# motor_drive.net
KiCad netlist of a schematic drawn in Altium Designer
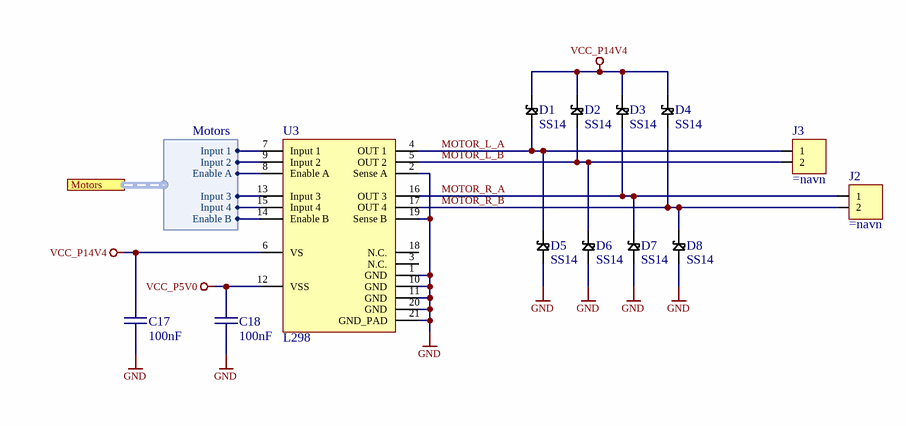
[diagram p0: motor_drive.SchDoc]

(export (version "E")
  (design (tool "Eeschema 10.0.6"))
  (components
    (comp (ref "C17")
      (value "100nF")
      (footprint "CAPC0603(1608)55_N")
      (description "X7R 50V 5%")
      (libsource (lib "OVLib_64") (part "CAP"))
    )
    (comp (ref "C18")
      (value "100nF")
      (footprint "CAPC0603(1608)55_N")
      (description "X7R 50V 5%")
      (libsource (lib "OVLib_64") (part "CAP"))
    )
    (comp (ref "D1")
      (value "SS14")
      (footprint "SMA_DO-214AC")
      (libsource (lib "OVLib_64") (part "SchottkyDiode"))
    )
    (comp (ref "D2")
      (value "SS14")
      (footprint "SMA_DO-214AC")
      (libsource (lib "OVLib_64") (part "SchottkyDiode"))
    )
    (comp (ref "D3")
      (value "SS14")
      (footprint "SMA_DO-214AC")
      (libsource (lib "OVLib_64") (part "SchottkyDiode"))
    )
    (comp (ref "D4")
      (value "SS14")
      (footprint "SMA_DO-214AC")
      (libsource (lib "OVLib_64") (part "SchottkyDiode"))
    )
    (comp (ref "D5")
      (value "SS14")
      (footprint "SMA_DO-214AC")
      (libsource (lib "OVLib_64") (part "SchottkyDiode"))
    )
    (comp (ref "D6")
      (value "SS14")
      (footprint "SMA_DO-214AC")
      (libsource (lib "OVLib_64") (part "SchottkyDiode"))
    )
    (comp (ref "D7")
      (value "SS14")
      (footprint "SMA_DO-214AC")
      (libsource (lib "OVLib_64") (part "SchottkyDiode"))
    )
    (comp (ref "D8")
      (value "SS14")
      (footprint "SMA_DO-214AC")
      (libsource (lib "OVLib_64") (part "SchottkyDiode"))
    )
    (comp (ref "J2")
      (value "~")
      (footprint "XT30_Female_Vertical")
      (description "Pris per del, For å koble ledninger sammen")
      (libsource (lib "OVLib_64") (part "2PConnector"))
    )
    (comp (ref "J3")
      (value "~")
      (footprint "XT30_Female_Vertical")
      (description "Pris per del, For å koble ledninger sammen")
      (libsource (lib "OVLib_64") (part "2PConnector"))
    )
    (comp (ref "U3")
      (value "L298")
      (footprint "SOIC127P1420X360_HS-21M")
      (description "Dual H Bridge")
      (libsource (lib "OVLib_64") (part "L298"))
    )
  )
  (nets
    (net (code "2") (name "/Enable A") (class "Default")
      (node (ref "U3") (pin "8") (pinfunction "Enable_A_8") (pintype "passive"))
    )
    (net (code "3") (name "/Enable B") (class "Default")
      (node (ref "U3") (pin "14") (pinfunction "Enable_B_14") (pintype "passive"))
    )
    (net (code "4") (name "/Input 1") (class "Default")
      (node (ref "U3") (pin "7") (pinfunction "Input_1_7") (pintype "passive"))
    )
    (net (code "5") (name "/Input 2") (class "Default")
      (node (ref "U3") (pin "9") (pinfunction "Input_2_9") (pintype "passive"))
    )
    (net (code "6") (name "/Input 3") (class "Default")
      (node (ref "U3") (pin "13") (pinfunction "Input_3_13") (pintype "passive"))
    )
    (net (code "7") (name "/Input 4") (class "Default")
      (node (ref "U3") (pin "15") (pinfunction "Input_4_15") (pintype "passive"))
    )
    (net (code "8") (name "/MOTOR_L_A") (class "Default")
      (node (ref "D1") (pin "1") (pinfunction "A_1") (pintype "passive"))
      (node (ref "D5") (pin "2") (pinfunction "K_2") (pintype "passive"))
      (node (ref "J3") (pin "1") (pinfunction "1_1") (pintype "passive"))
      (node (ref "U3") (pin "4") (pinfunction "OUT_1_4") (pintype "passive"))
    )
    (net (code "9") (name "/MOTOR_L_B") (class "Default")
      (node (ref "D2") (pin "1") (pinfunction "A_1") (pintype "passive"))
      (node (ref "D6") (pin "2") (pinfunction "K_2") (pintype "passive"))
      (node (ref "J3") (pin "2") (pinfunction "2_2") (pintype "passive"))
      (node (ref "U3") (pin "5") (pinfunction "OUT_2_5") (pintype "passive"))
    )
    (net (code "10") (name "/MOTOR_R_A") (class "Default")
      (node (ref "D3") (pin "1") (pinfunction "A_1") (pintype "passive"))
      (node (ref "D7") (pin "2") (pinfunction "K_2") (pintype "passive"))
      (node (ref "J2") (pin "1") (pinfunction "1_1") (pintype "passive"))
      (node (ref "U3") (pin "16") (pinfunction "OUT_3_16") (pintype "passive"))
    )
    (net (code "11") (name "/MOTOR_R_B") (class "Default")
      (node (ref "D4") (pin "1") (pinfunction "A_1") (pintype "passive"))
      (node (ref "D8") (pin "2") (pinfunction "K_2") (pintype "passive"))
      (node (ref "J2") (pin "2") (pinfunction "2_2") (pintype "passive"))
      (node (ref "U3") (pin "17") (pinfunction "OUT_4_17") (pintype "passive"))
    )
    (net (code "13") (name "GND") (class "Default")
      (node (ref "C17") (pin "1") (pinfunction "1_1") (pintype "passive"))
      (node (ref "C18") (pin "1") (pinfunction "1_1") (pintype "passive"))
      (node (ref "D5") (pin "1") (pinfunction "A_1") (pintype "passive"))
      (node (ref "D6") (pin "1") (pinfunction "A_1") (pintype "passive"))
      (node (ref "D7") (pin "1") (pinfunction "A_1") (pintype "passive"))
      (node (ref "D8") (pin "1") (pinfunction "A_1") (pintype "passive"))
      (node (ref "U3") (pin "1") (pinfunction "GND_1") (pintype "passive"))
      (node (ref "U3") (pin "10") (pinfunction "GND_10") (pintype "passive"))
      (node (ref "U3") (pin "11") (pinfunction "GND_11") (pintype "passive"))
      (node (ref "U3") (pin "19") (pinfunction "Sense_B_19") (pintype "passive"))
      (node (ref "U3") (pin "2") (pinfunction "Sense_A_2") (pintype "passive"))
      (node (ref "U3") (pin "20") (pinfunction "GND_20") (pintype "passive"))
      (node (ref "U3") (pin "21") (pinfunction "GND_PAD_21") (pintype "passive"))
    )
    (net (code "14") (name "VCC_P5V0") (class "Default")
      (node (ref "C18") (pin "2") (pinfunction "2_2") (pintype "passive"))
      (node (ref "U3") (pin "12") (pinfunction "VSS_12") (pintype "passive"))
    )
    (net (code "15") (name "VCC_P14V4") (class "Default")
      (node (ref "C17") (pin "2") (pinfunction "2_2") (pintype "passive"))
      (node (ref "D1") (pin "2") (pinfunction "K_2") (pintype "passive"))
      (node (ref "D2") (pin "2") (pinfunction "K_2") (pintype "passive"))
      (node (ref "D3") (pin "2") (pinfunction "K_2") (pintype "passive"))
      (node (ref "D4") (pin "2") (pinfunction "K_2") (pintype "passive"))
      (node (ref "U3") (pin "6") (pinfunction "VS_6") (pintype "passive"))
    )
    (net (code "16") (name "unconnected-(U3-N.C.-Pad3)") (class "Default")
      (node (ref "U3") (pin "3") (pinfunction "N.C._3") (pintype "passive"))
    )
    (net (code "17") (name "unconnected-(U3-N.C.-Pad18)") (class "Default")
      (node (ref "U3") (pin "18") (pinfunction "N.C._18") (pintype "passive"))
    )
  )
)
